# SCH_New-Project_2024-03-02.net
KiCad netlist of a schematic drawn in EasyEDA
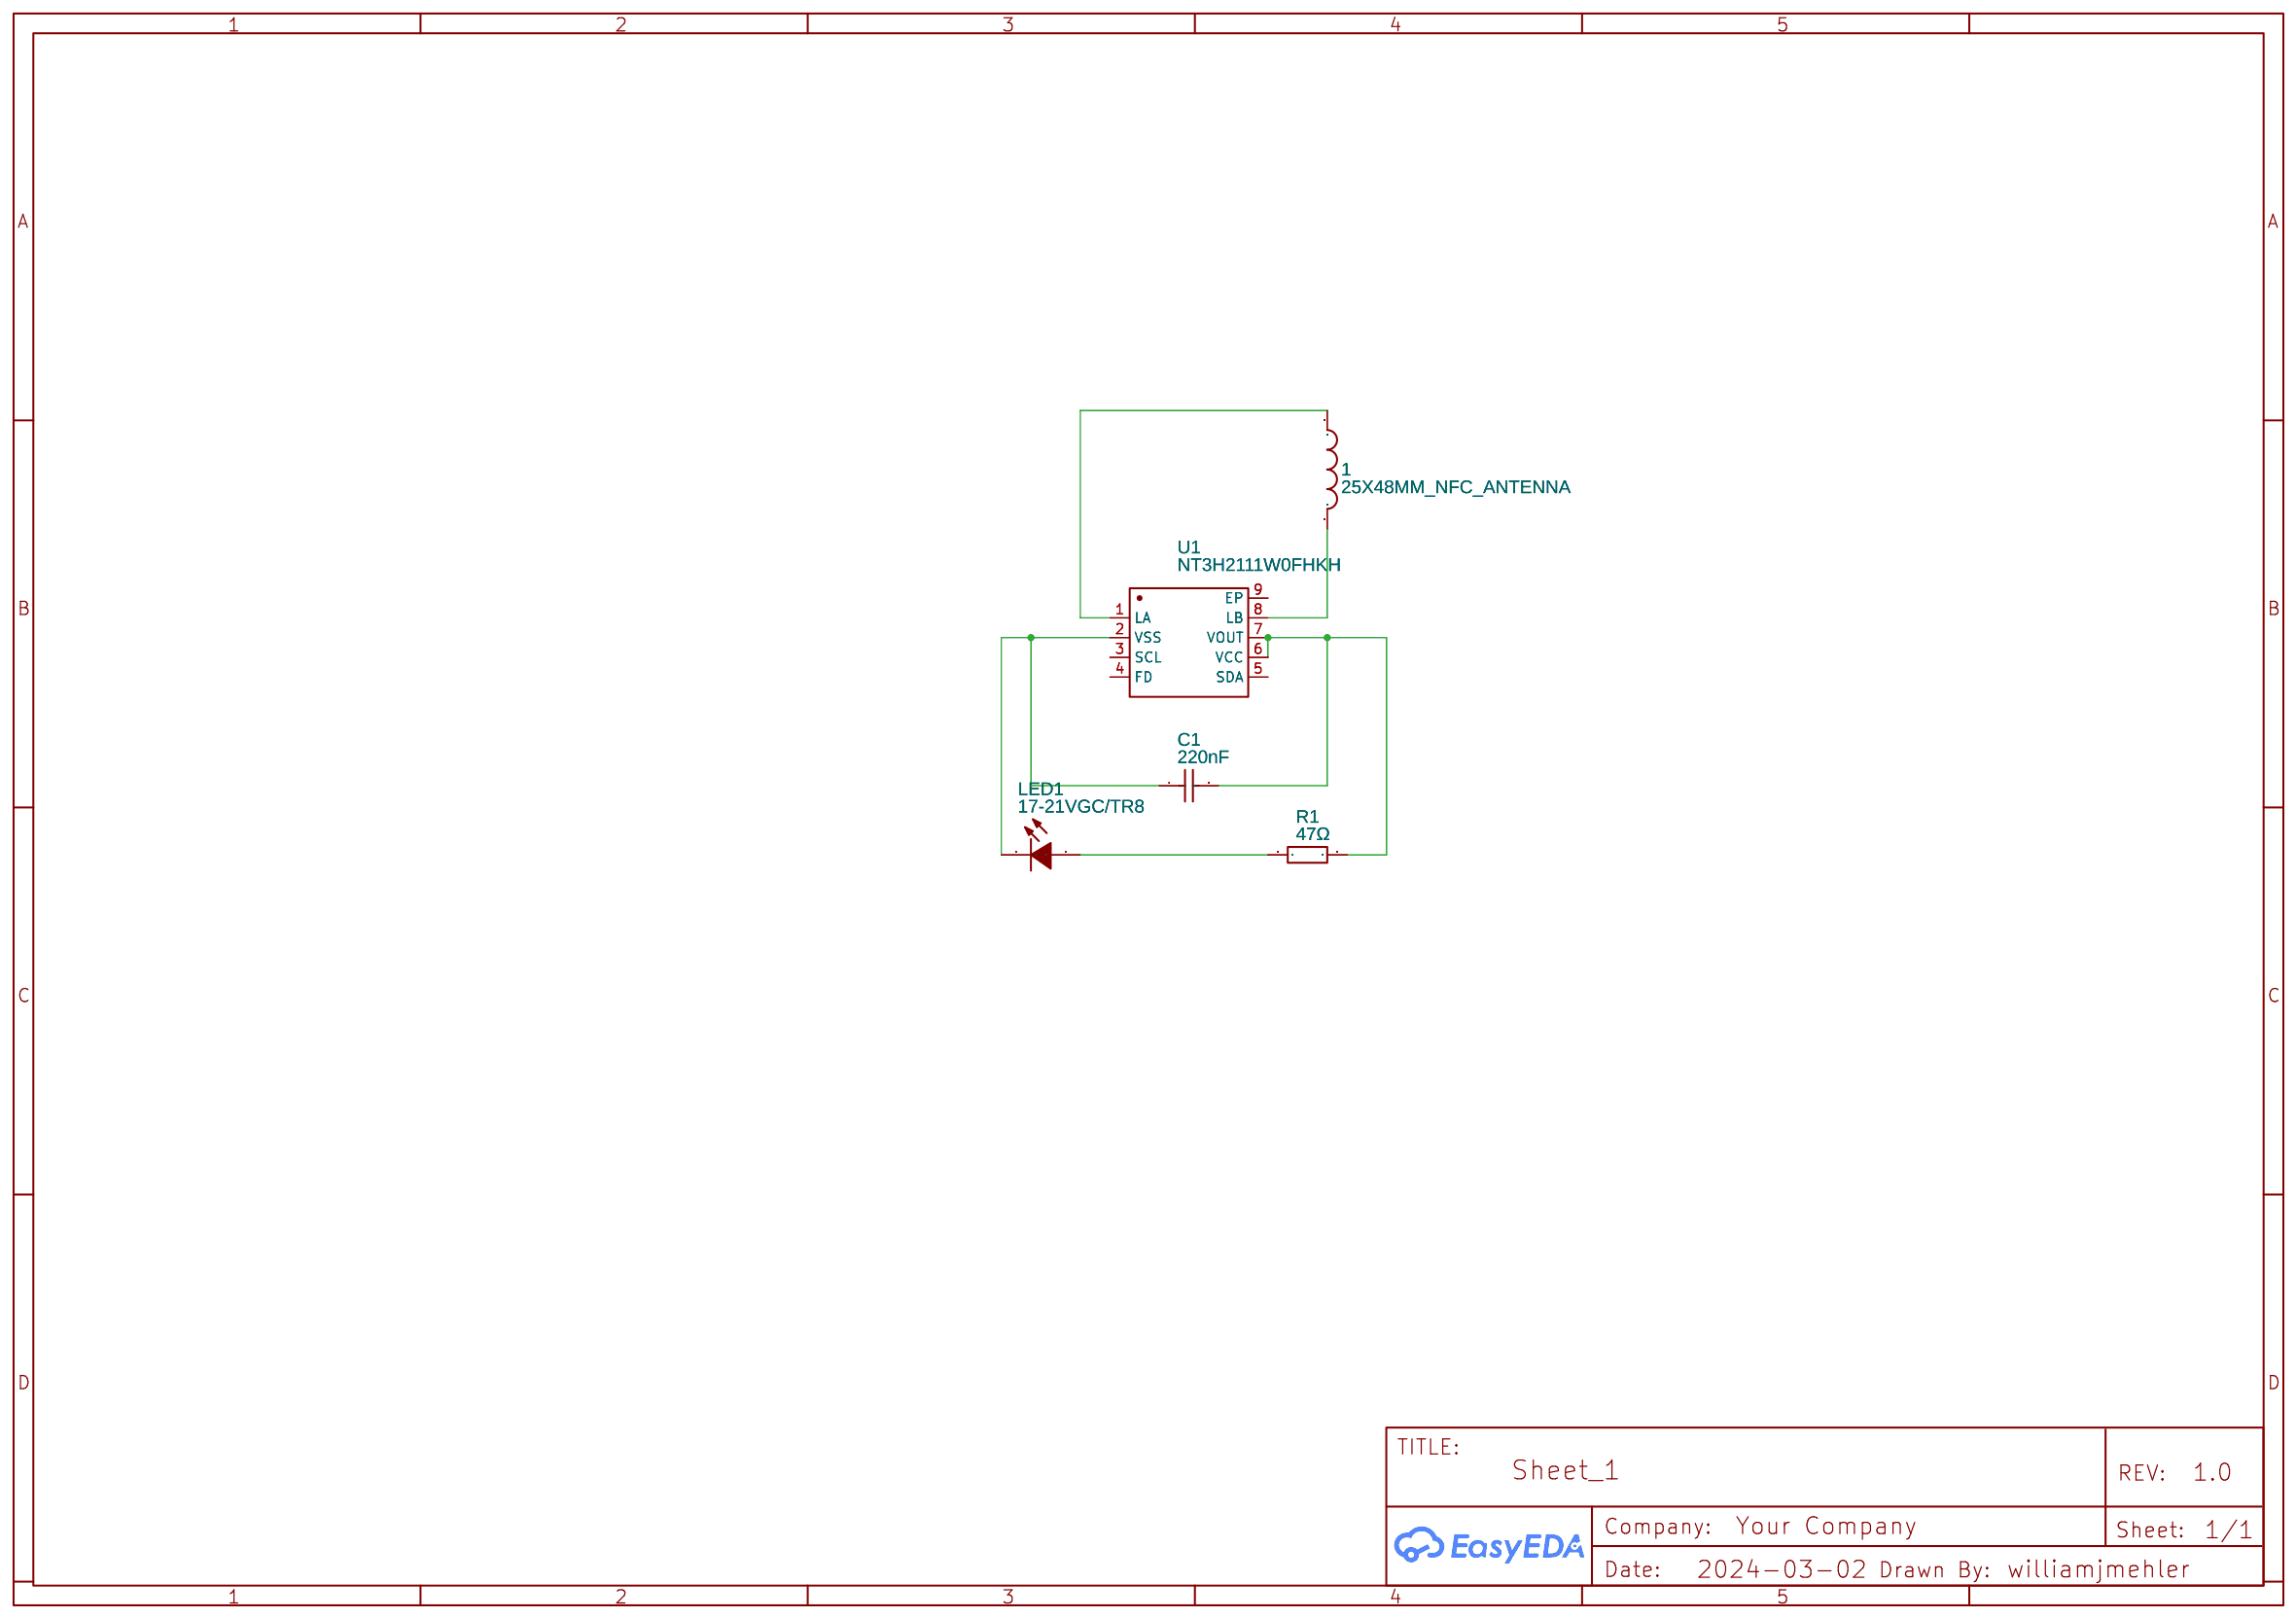
[diagram p0: schematic sheet]

(export (version "E")
  (design (tool "Eeschema 10.0.6"))
  (components
    (comp (ref "1") (value "25X48MM_NFC_ANTENNA") (libsource (lib "") (part "25X48MM_NFC_ANTENNA")))
    (comp (ref "C1")
      (value "220nF")
      (fields
        (field (name "Manufacturer Part") "CL10B224KA8NNNC")
        (field (name "Manufacturer") "SAMSUNG(三星)")
      )
      (libsource (lib "") (part "CL10B224KA8NNNC"))
    )
    (comp (ref "LED1")
      (value "17-21VGC/TR8")
      (fields (field (name "Manufacturer") "EVERLIGHT(亿光)"))
      (libsource (lib "") (part "17-21VGC/TR8"))
    )
    (comp (ref "R1")
      (value "47Ω")
      (fields
        (field (name "Manufacturer Part") "0603WAF470JT5E")
        (field (name "Manufacturer") "UNI-ROYAL(厚声)")
      )
      (libsource (lib "") (part "0603WAF470JT5E"))
    )
    (comp (ref "U1")
      (value "NT3H2111W0FHKH")
      (fields (field (name "Manufacturer") "NXP(恩智浦)"))
      (libsource (lib "") (part "NT3H2111W0FHKH"))
    )
  )
  (nets
    (net (code "1") (name "Net-(LED1-+)") (class "Default")
      (node (ref "LED1") (pin "2") (pinfunction "+_2") (pintype "unspecified"))
      (node (ref "R1") (pin "1") (pinfunction "1_1") (pintype "input"))
    )
    (net (code "2") (name "Net-(LED1--)") (class "Default")
      (node (ref "C1") (pin "1") (pinfunction "1_1") (pintype "input"))
      (node (ref "LED1") (pin "1") (pinfunction "-_1") (pintype "unspecified"))
      (node (ref "U1") (pin "2") (pinfunction "VSS_2") (pintype "unspecified"))
    )
    (net (code "3") (name "Net-(U1-LA)") (class "Default")
      (node (ref "1") (pin "P$1") (pinfunction "P$1_P$1") (pintype "bidirectional"))
      (node (ref "U1") (pin "1") (pinfunction "LA_1") (pintype "unspecified"))
    )
    (net (code "4") (name "Net-(U1-LB)") (class "Default")
      (node (ref "1") (pin "P$2") (pinfunction "P$2_P$2") (pintype "bidirectional"))
      (node (ref "U1") (pin "8") (pinfunction "LB_8") (pintype "unspecified"))
    )
    (net (code "5") (name "Net-(U1-VCC)") (class "Default")
      (node (ref "C1") (pin "2") (pinfunction "2_2") (pintype "input"))
      (node (ref "R1") (pin "2") (pinfunction "2_2") (pintype "input"))
      (node (ref "U1") (pin "6") (pinfunction "VCC_6") (pintype "unspecified"))
      (node (ref "U1") (pin "7") (pinfunction "VOUT_7") (pintype "unspecified"))
    )
    (net (code "6") (name "unconnected-(U1-EP-Pad9)") (class "Default")
      (node (ref "U1") (pin "9") (pinfunction "EP_9") (pintype "unspecified"))
    )
    (net (code "7") (name "unconnected-(U1-FD-Pad4)") (class "Default")
      (node (ref "U1") (pin "4") (pinfunction "FD_4") (pintype "unspecified"))
    )
    (net (code "8") (name "unconnected-(U1-SCL-Pad3)") (class "Default")
      (node (ref "U1") (pin "3") (pinfunction "SCL_3") (pintype "unspecified"))
    )
    (net (code "9") (name "unconnected-(U1-SDA-Pad5)") (class "Default")
      (node (ref "U1") (pin "5") (pinfunction "SDA_5") (pintype "unspecified"))
    )
  )
)
